# amiga_ps2_adapter.net
KiCad netlist of a schematic drawn in EAGLE
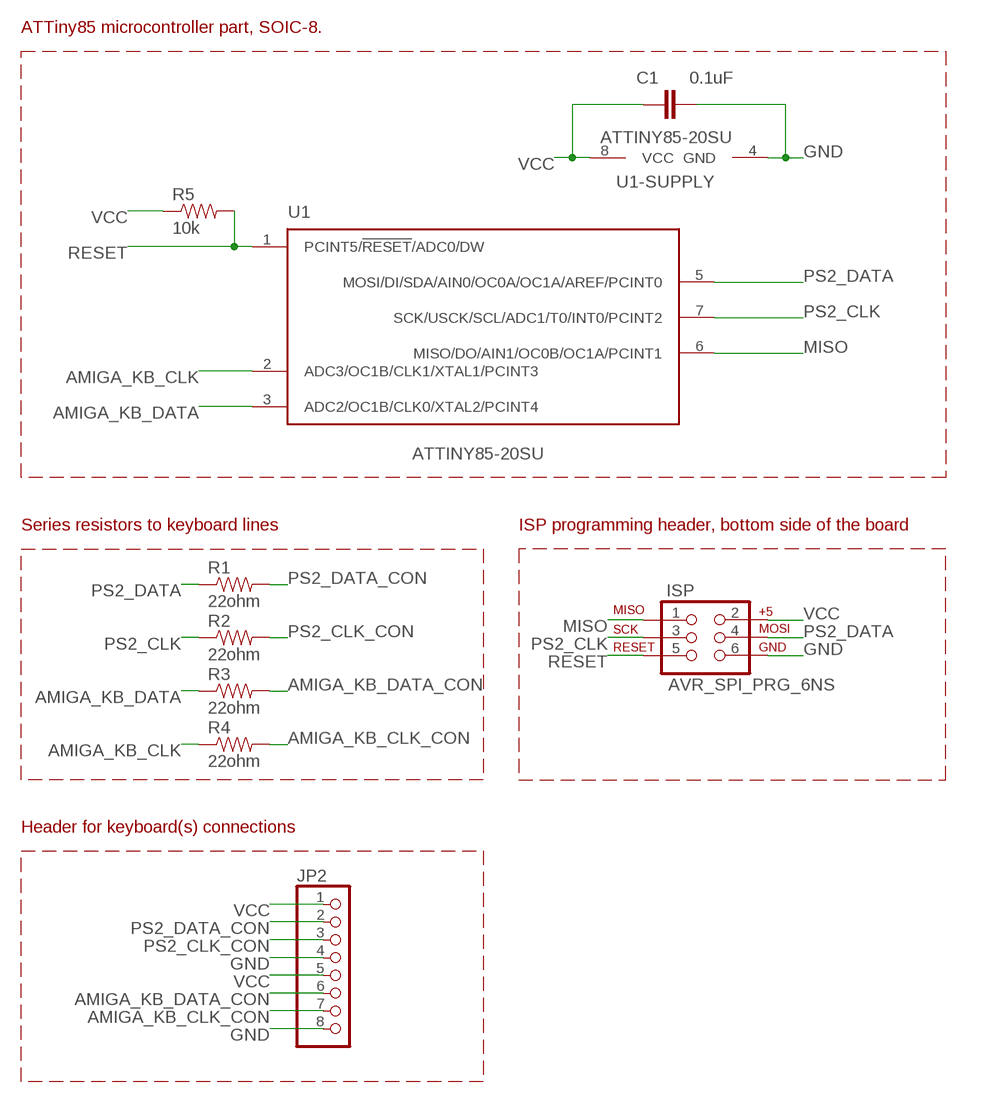
[diagram p0: schematic, sheet 1]

(export (version "E")
  (design (tool "Eeschema 10.0.6"))
  (components
    (comp (ref "C1")
      (value "0.1uF")
      (footprint "eagle-import:0603-CAP")
      (libsource (lib "eagle-import") (part "CAP0603-CAP"))
    )
    (comp (ref "ISP")
      (value "AVR_SPI_PRG_6NS")
      (footprint "eagle-import:2X3-NS")
      (libsource (lib "eagle-import") (part "AVR_SPI_PRG_6NS"))
    )
    (comp (ref "JP2")
      (value "HEADER-1X8ROUND")
      (footprint "eagle-import:1X08_ROUND")
      (libsource (lib "eagle-import") (part "HEADER-1X8ROUND"))
    )
    (comp (ref "R1")
      (value "22ohm")
      (footprint "eagle-import:0603-RES")
      (libsource (lib "eagle-import") (part "RESISTOR0603-RES"))
    )
    (comp (ref "R2")
      (value "22ohm")
      (footprint "eagle-import:0603-RES")
      (libsource (lib "eagle-import") (part "RESISTOR0603-RES"))
    )
    (comp (ref "R3")
      (value "22ohm")
      (footprint "eagle-import:0603-RES")
      (libsource (lib "eagle-import") (part "RESISTOR0603-RES"))
    )
    (comp (ref "R4")
      (value "22ohm")
      (footprint "eagle-import:0603-RES")
      (libsource (lib "eagle-import") (part "RESISTOR0603-RES"))
    )
    (comp (ref "R5")
      (value "10k")
      (footprint "eagle-import:0603-RES")
      (libsource (lib "eagle-import") (part "RESISTOR0603-RES"))
    )
    (comp (ref "U1")
      (value "ATTINY85-20SU")
      (footprint "eagle-import:SOIC-8")
      (fields (field (name "MANUFACTURER") "Atmel"))
      (libsource (lib "eagle-import") (part "ATTINY5-?20SU8"))
    )
  )
  (nets
    (net (code "1") (name "AMIGA_KB_CLK") (class "Default")
      (node (ref "R4") (pin "1") (pinfunction "1_1") (pintype "passive"))
      (node (ref "U1") (pin "2") (pinfunction "ADC3/OC1B/CLK1/XTAL1/PCINT3_2") (pintype "bidirectional"))
    )
    (net (code "2") (name "AMIGA_KB_CLK_CON") (class "Default")
      (node (ref "JP2") (pin "7") (pinfunction "7_7") (pintype "passive"))
      (node (ref "R4") (pin "2") (pinfunction "2_2") (pintype "passive"))
    )
    (net (code "3") (name "AMIGA_KB_DATA") (class "Default")
      (node (ref "R3") (pin "1") (pinfunction "1_1") (pintype "passive"))
      (node (ref "U1") (pin "3") (pinfunction "ADC2/OC1B/CLK0/XTAL2/PCINT4_3") (pintype "bidirectional"))
    )
    (net (code "4") (name "AMIGA_KB_DATA_CON") (class "Default")
      (node (ref "JP2") (pin "6") (pinfunction "6_6") (pintype "passive"))
      (node (ref "R3") (pin "2") (pinfunction "2_2") (pintype "passive"))
    )
    (net (code "5") (name "GND") (class "Default")
      (node (ref "C1") (pin "2") (pinfunction "2_2") (pintype "passive"))
      (node (ref "ISP") (pin "6") (pinfunction "6_6") (pintype "passive"))
      (node (ref "JP2") (pin "4") (pinfunction "4_4") (pintype "passive"))
      (node (ref "JP2") (pin "8") (pinfunction "8_8") (pintype "passive"))
      (node (ref "U1") (pin "4") (pinfunction "GND_4") (pintype "power_in"))
    )
    (net (code "6") (name "MISO") (class "Default")
      (node (ref "ISP") (pin "1") (pinfunction "1_1") (pintype "passive"))
      (node (ref "U1") (pin "6") (pinfunction "MISO/DO/AIN1/OC0B/OC1A/PCINT1_6") (pintype "bidirectional"))
    )
    (net (code "7") (name "PS2_CLK") (class "Default")
      (node (ref "ISP") (pin "3") (pinfunction "3_3") (pintype "passive"))
      (node (ref "R2") (pin "1") (pinfunction "1_1") (pintype "passive"))
      (node (ref "U1") (pin "7") (pinfunction "SCK/USCK/SCL/ADC1/T0/INT0/PCINT2_7") (pintype "bidirectional"))
    )
    (net (code "8") (name "PS2_CLK_CON") (class "Default")
      (node (ref "JP2") (pin "3") (pinfunction "3_3") (pintype "passive"))
      (node (ref "R2") (pin "2") (pinfunction "2_2") (pintype "passive"))
    )
    (net (code "9") (name "PS2_DATA") (class "Default")
      (node (ref "ISP") (pin "4") (pinfunction "4_4") (pintype "passive"))
      (node (ref "R1") (pin "1") (pinfunction "1_1") (pintype "passive"))
      (node (ref "U1") (pin "5") (pinfunction "MOSI/DI/SDA/AIN0/OC0A/OC1A/AREF/PCINT0_5") (pintype "bidirectional"))
    )
    (net (code "10") (name "PS2_DATA_CON") (class "Default")
      (node (ref "JP2") (pin "2") (pinfunction "2_2") (pintype "passive"))
      (node (ref "R1") (pin "2") (pinfunction "2_2") (pintype "passive"))
    )
    (net (code "11") (name "RESET") (class "Default")
      (node (ref "ISP") (pin "5") (pinfunction "5_5") (pintype "passive"))
      (node (ref "R5") (pin "2") (pinfunction "2_2") (pintype "passive"))
      (node (ref "U1") (pin "1") (pinfunction "PCINT5/~{RESET}/ADC0/DW_1") (pintype "bidirectional"))
    )
    (net (code "12") (name "VCC") (class "Default")
      (node (ref "C1") (pin "1") (pinfunction "1_1") (pintype "passive"))
      (node (ref "ISP") (pin "2") (pinfunction "2_2") (pintype "passive"))
      (node (ref "JP2") (pin "1") (pinfunction "1_1") (pintype "passive"))
      (node (ref "JP2") (pin "5") (pinfunction "5_5") (pintype "passive"))
      (node (ref "R5") (pin "1") (pinfunction "1_1") (pintype "passive"))
      (node (ref "U1") (pin "8") (pinfunction "VCC_8") (pintype "power_in"))
    )
  )
)
